# BAM_Reference_R2_1_1.net
KiCad netlist of a schematic drawn in EAGLE
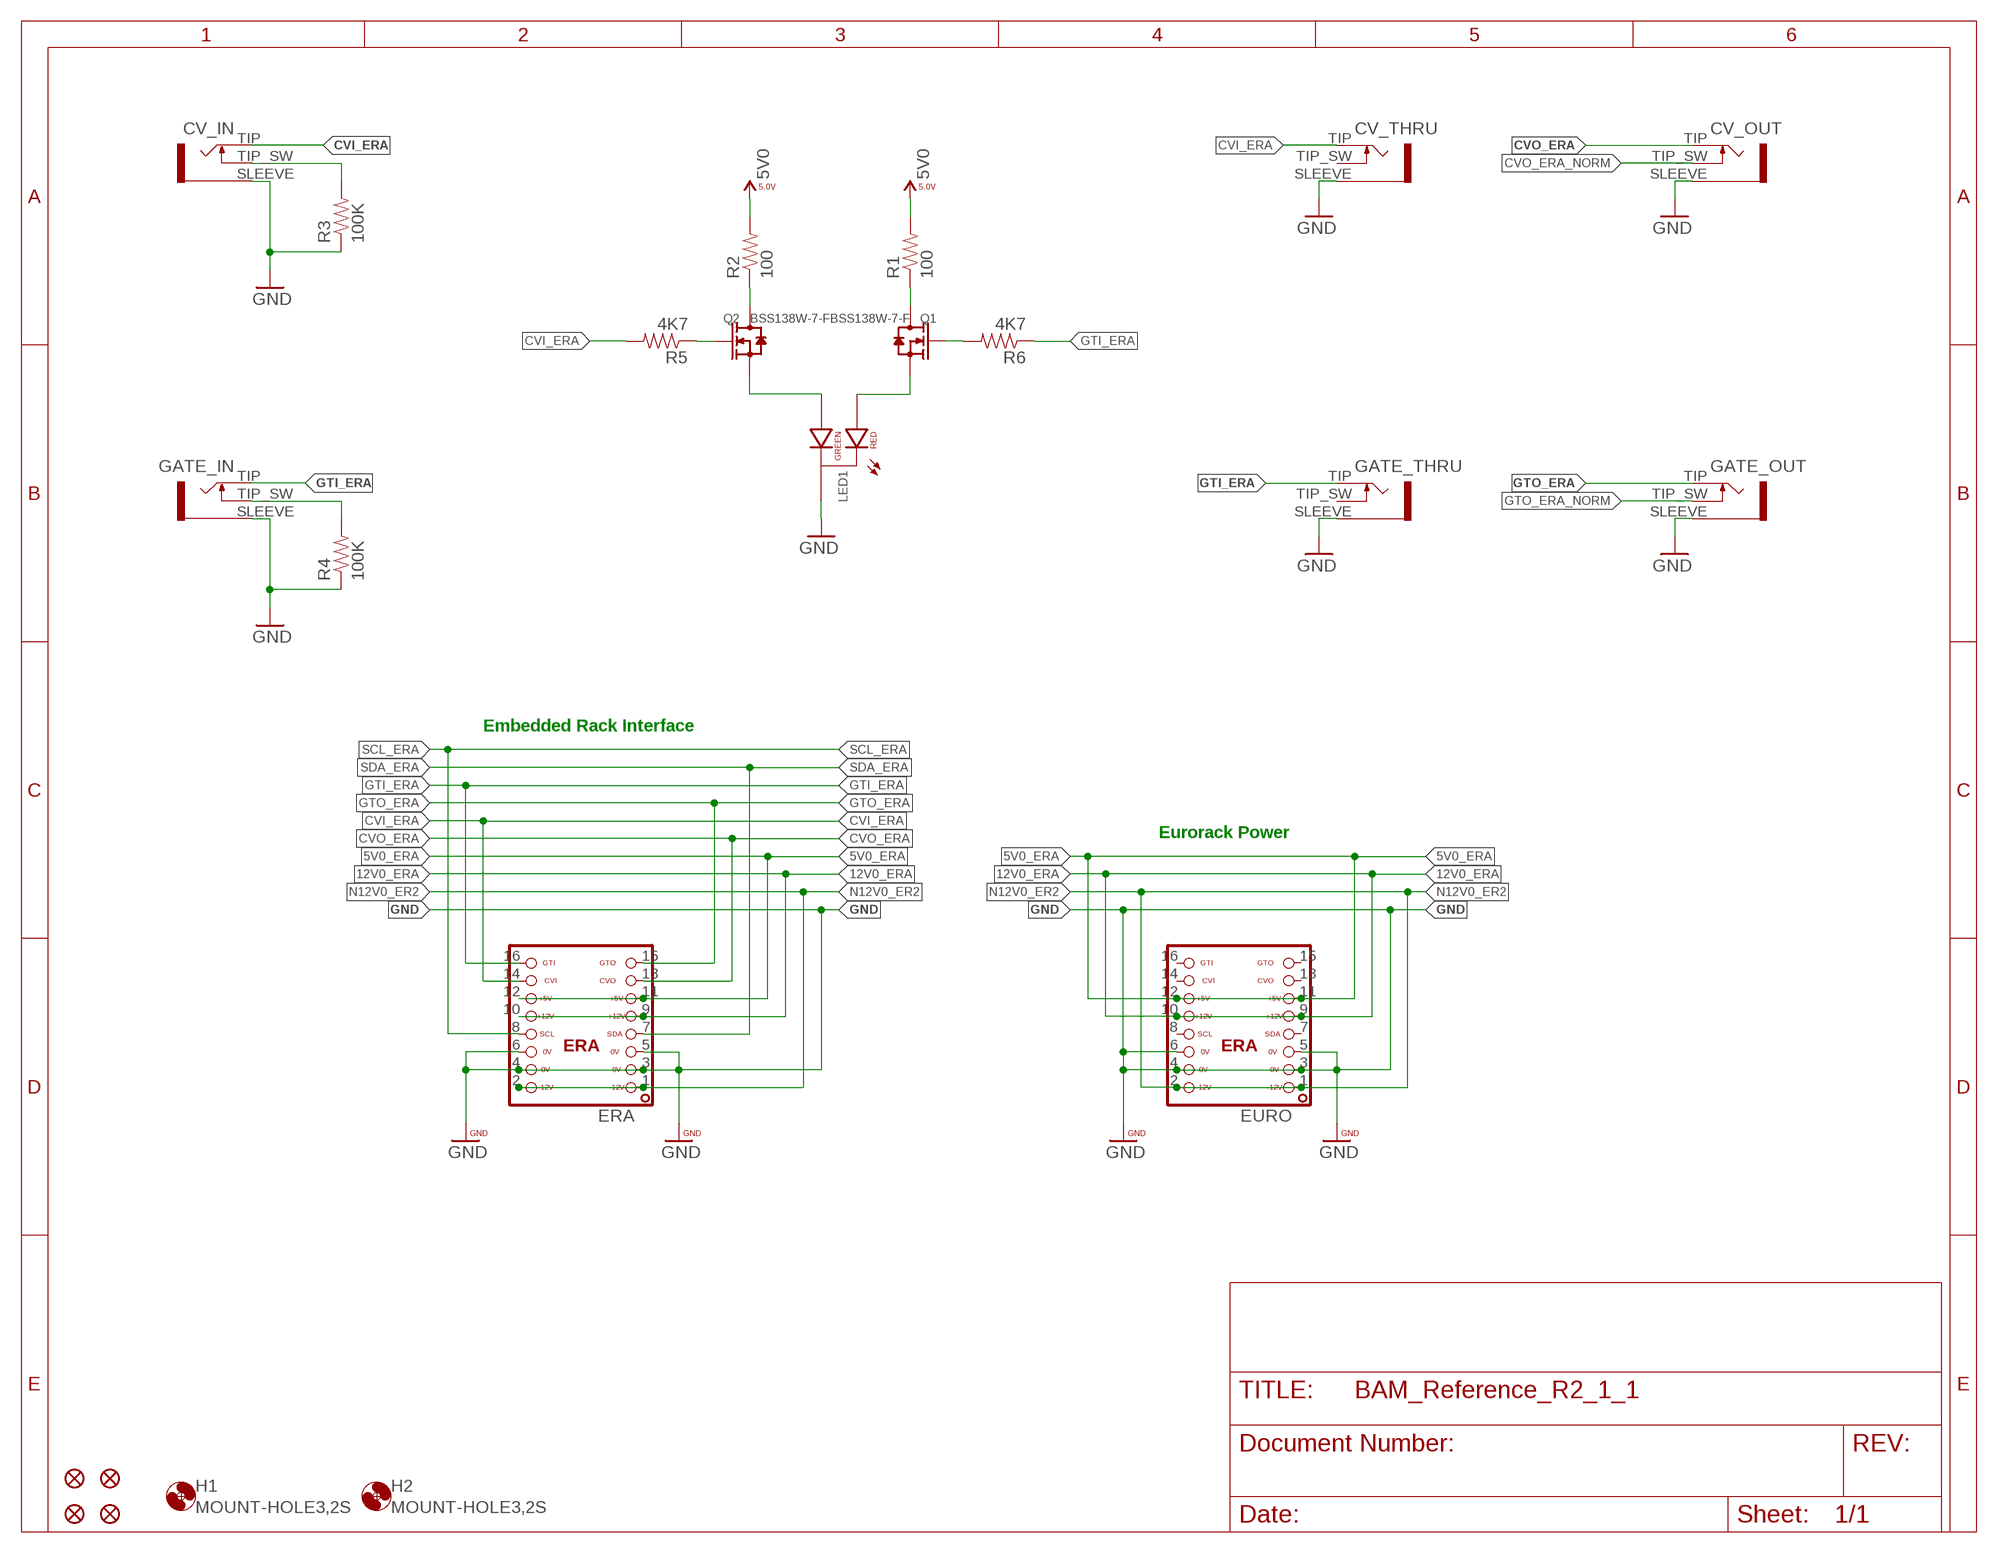
[diagram p0: schematic, sheet 1]

(export (version "E")
  (design (tool "Eeschema 10.0.6"))
  (components
    (comp (ref "CV_IN")
      (value "JACK-3_5MM-MONO-SW-MJ_3502")
      (footprint "eagle-import:MJ-3502")
      (libsource (lib "eagle-import") (part "oXo_Connectors_JACK-3_5MM-MONO-SW-MJ_3502"))
    )
    (comp (ref "CV_OUT")
      (value "JACK-3_5MM-MONO-SW-MJ_3502")
      (footprint "eagle-import:MJ-3502")
      (libsource (lib "eagle-import") (part "JACK-3_5MM-MONO-SW-MJ_3502"))
    )
    (comp (ref "CV_THRU")
      (value "JACK-3_5MM-MONO-SW-MJ_3502")
      (footprint "eagle-import:MJ-3502")
      (libsource (lib "eagle-import") (part "JACK-3_5MM-MONO-SW-MJ_3502"))
    )
    (comp (ref "ERA")
      (value "ERA-SHROUD")
      (footprint "eagle-import:ERA")
      (libsource (lib "eagle-import") (part "ERA-SHROUD"))
    )
    (comp (ref "EURO")
      (value "ERA-SHROUD")
      (footprint "eagle-import:ERA")
      (libsource (lib "eagle-import") (part "ERA-SHROUD"))
    )
    (comp (ref "FID1")
      (value "FIDUCIALUFIDUCIAL")
      (footprint "eagle-import:MICRO-FIDUCIAL")
      (libsource (lib "eagle-import") (part "FIDUCIALUFIDUCIAL"))
    )
    (comp (ref "FID2")
      (value "FIDUCIALUFIDUCIAL")
      (footprint "eagle-import:MICRO-FIDUCIAL")
      (libsource (lib "eagle-import") (part "FIDUCIALUFIDUCIAL"))
    )
    (comp (ref "FID3")
      (value "FIDUCIALUFIDUCIAL")
      (footprint "eagle-import:MICRO-FIDUCIAL")
      (libsource (lib "eagle-import") (part "FIDUCIALUFIDUCIAL"))
    )
    (comp (ref "FID4")
      (value "FIDUCIALUFIDUCIAL")
      (footprint "eagle-import:MICRO-FIDUCIAL")
      (libsource (lib "eagle-import") (part "FIDUCIALUFIDUCIAL"))
    )
    (comp (ref "GATE_IN")
      (value "JACK-3_5MM-MONO-SW-MJ_3502")
      (footprint "eagle-import:MJ-3502")
      (libsource (lib "eagle-import") (part "oXo_Connectors_JACK-3_5MM-MONO-SW-MJ_3502"))
    )
    (comp (ref "GATE_OUT")
      (value "JACK-3_5MM-MONO-SW-MJ_3502")
      (footprint "eagle-import:MJ-3502")
      (libsource (lib "eagle-import") (part "JACK-3_5MM-MONO-SW-MJ_3502"))
    )
    (comp (ref "GATE_THRU")
      (value "JACK-3_5MM-MONO-SW-MJ_3502")
      (footprint "eagle-import:MJ-3502")
      (libsource (lib "eagle-import") (part "JACK-3_5MM-MONO-SW-MJ_3502"))
    )
    (comp (ref "H1")
      (value "MOUNT-HOLE3,2S")
      (footprint "eagle-import:3,2,SMALL")
      (libsource (lib "eagle-import") (part "MOUNT-HOLE3,2S"))
    )
    (comp (ref "H2")
      (value "MOUNT-HOLE3,2S")
      (footprint "eagle-import:3,2,SMALL")
      (libsource (lib "eagle-import") (part "MOUNT-HOLE3,2S"))
    )
    (comp (ref "LED1")
      (value "LED-RG-CC-PTH-G18500")
      (footprint "eagle-import:LED-RG-PANEL")
      (libsource (lib "eagle-import") (part "LED-RG-CC-PTH-G18500"))
    )
    (comp (ref "Q1")
      (value "BSS138W-7-F")
      (footprint "eagle-import:SOT-23")
      (libsource (lib "eagle-import") (part "SMD-MOSFET-N-CH-50V-200MA-BSS138W-7-F(SOT-23)"))
    )
    (comp (ref "Q2")
      (value "BSS138W-7-F")
      (footprint "eagle-import:SOT-23")
      (libsource (lib "eagle-import") (part "SMD-MOSFET-N-CH-50V-200MA-BSS138W-7-F(SOT-23)"))
    )
    (comp (ref "R1")
      (value "100")
      (footprint "eagle-import:0603-RES")
      (libsource (lib "eagle-import") (part "RESISTOR0603"))
    )
    (comp (ref "R2")
      (value "100")
      (footprint "eagle-import:0603-RES")
      (libsource (lib "eagle-import") (part "RESISTOR0603"))
    )
    (comp (ref "R3")
      (value "100K")
      (footprint "eagle-import:0603-RES")
      (libsource (lib "eagle-import") (part "RESISTOR0603"))
    )
    (comp (ref "R4")
      (value "100K")
      (footprint "eagle-import:0603-RES")
      (libsource (lib "eagle-import") (part "RESISTOR0603"))
    )
    (comp (ref "R5")
      (value "4K7")
      (footprint "eagle-import:0603-RES")
      (libsource (lib "eagle-import") (part "RESISTOR0603"))
    )
    (comp (ref "R6")
      (value "4K7")
      (footprint "eagle-import:0603-RES")
      (libsource (lib "eagle-import") (part "RESISTOR0603"))
    )
  )
  (nets
    (net (code "1") (name "5V0") (class "Default")
      (node (ref "R1") (pin "2") (pinfunction "2_2") (pintype "passive"))
      (node (ref "R2") (pin "2") (pinfunction "2_2") (pintype "passive"))
    )
    (net (code "2") (name "5V0_ERA") (class "Default")
      (node (ref "ERA") (pin "11") (pinfunction "11_11") (pintype "passive"))
      (node (ref "ERA") (pin "12") (pinfunction "12_12") (pintype "passive"))
      (node (ref "EURO") (pin "11") (pinfunction "11_11") (pintype "passive"))
      (node (ref "EURO") (pin "12") (pinfunction "12_12") (pintype "passive"))
    )
    (net (code "3") (name "12V0_ERA") (class "Default")
      (node (ref "ERA") (pin "10") (pinfunction "10_10") (pintype "passive"))
      (node (ref "ERA") (pin "9") (pinfunction "9_9") (pintype "passive"))
      (node (ref "EURO") (pin "10") (pinfunction "10_10") (pintype "passive"))
      (node (ref "EURO") (pin "9") (pinfunction "9_9") (pintype "passive"))
    )
    (net (code "4") (name "CVI_ERA") (class "Default")
      (node (ref "CV_IN") (pin "TIP") (pinfunction "TIP_TIP") (pintype "passive"))
      (node (ref "CV_THRU") (pin "TIP") (pinfunction "TIP_TIP") (pintype "passive"))
      (node (ref "ERA") (pin "14") (pinfunction "14_14") (pintype "passive"))
      (node (ref "R5") (pin "2") (pinfunction "2_2") (pintype "passive"))
    )
    (net (code "5") (name "CVO_ERA") (class "Default")
      (node (ref "CV_OUT") (pin "TIP") (pinfunction "TIP_TIP") (pintype "passive"))
      (node (ref "ERA") (pin "13") (pinfunction "13_13") (pintype "passive"))
    )
    (net (code "6") (name "CVO_ERA_NORM") (class "Default")
      (node (ref "CV_OUT") (pin "TIP_SW") (pinfunction "TIP_SW_TIP_SW") (pintype "passive"))
    )
    (net (code "7") (name "GND") (class "Default")
      (node (ref "CV_IN") (pin "SLEEVE") (pinfunction "SLEEVE_SLEEVE") (pintype "passive"))
      (node (ref "CV_OUT") (pin "SLEEVE") (pinfunction "SLEEVE_SLEEVE") (pintype "passive"))
      (node (ref "CV_THRU") (pin "SLEEVE") (pinfunction "SLEEVE_SLEEVE") (pintype "passive"))
      (node (ref "ERA") (pin "3") (pinfunction "3_3") (pintype "passive"))
      (node (ref "ERA") (pin "4") (pinfunction "4_4") (pintype "passive"))
      (node (ref "ERA") (pin "5") (pinfunction "5_5") (pintype "passive"))
      (node (ref "ERA") (pin "6") (pinfunction "6_6") (pintype "passive"))
      (node (ref "EURO") (pin "3") (pinfunction "3_3") (pintype "passive"))
      (node (ref "EURO") (pin "4") (pinfunction "4_4") (pintype "passive"))
      (node (ref "EURO") (pin "5") (pinfunction "5_5") (pintype "passive"))
      (node (ref "EURO") (pin "6") (pinfunction "6_6") (pintype "passive"))
      (node (ref "GATE_IN") (pin "SLEEVE") (pinfunction "SLEEVE_SLEEVE") (pintype "passive"))
      (node (ref "GATE_OUT") (pin "SLEEVE") (pinfunction "SLEEVE_SLEEVE") (pintype "passive"))
      (node (ref "GATE_THRU") (pin "SLEEVE") (pinfunction "SLEEVE_SLEEVE") (pintype "passive"))
      (node (ref "LED1") (pin "CC") (pinfunction "CATHODE_CC") (pintype "bidirectional"))
      (node (ref "R3") (pin "1") (pinfunction "1_1") (pintype "passive"))
      (node (ref "R4") (pin "1") (pinfunction "1_1") (pintype "passive"))
    )
    (net (code "8") (name "GTI_ERA") (class "Default")
      (node (ref "ERA") (pin "16") (pinfunction "16_16") (pintype "passive"))
      (node (ref "GATE_IN") (pin "TIP") (pinfunction "TIP_TIP") (pintype "passive"))
      (node (ref "GATE_THRU") (pin "TIP") (pinfunction "TIP_TIP") (pintype "passive"))
      (node (ref "R6") (pin "1") (pinfunction "1_1") (pintype "passive"))
    )
    (net (code "9") (name "GTO_ERA") (class "Default")
      (node (ref "ERA") (pin "15") (pinfunction "15_15") (pintype "passive"))
      (node (ref "GATE_OUT") (pin "TIP") (pinfunction "TIP_TIP") (pintype "passive"))
    )
    (net (code "10") (name "GTO_ERA_NORM") (class "Default")
      (node (ref "GATE_OUT") (pin "TIP_SW") (pinfunction "TIP_SW_TIP_SW") (pintype "passive"))
    )
    (net (code "11") (name "N12V0_ER2") (class "Default")
      (node (ref "ERA") (pin "1") (pinfunction "1_1") (pintype "passive"))
      (node (ref "ERA") (pin "2") (pinfunction "2_2") (pintype "passive"))
      (node (ref "EURO") (pin "1") (pinfunction "1_1") (pintype "passive"))
      (node (ref "EURO") (pin "2") (pinfunction "2_2") (pintype "passive"))
    )
    (net (code "12") (name "Net-(CV_IN-PadTIP_SW)") (class "Default")
      (node (ref "CV_IN") (pin "TIP_SW") (pinfunction "TIP_SW_TIP_SW") (pintype "passive"))
      (node (ref "R3") (pin "2") (pinfunction "2_2") (pintype "passive"))
    )
    (net (code "13") (name "Net-(GATE_IN-PadTIP_SW)") (class "Default")
      (node (ref "GATE_IN") (pin "TIP_SW") (pinfunction "TIP_SW_TIP_SW") (pintype "passive"))
      (node (ref "R4") (pin "2") (pinfunction "2_2") (pintype "passive"))
    )
    (net (code "14") (name "Net-(LED1-GREEN_CATHODE)") (class "Default")
      (node (ref "LED1") (pin "GREEN") (pinfunction "GREEN_CATHODE_GREEN") (pintype "bidirectional"))
      (node (ref "Q2") (pin "2") (pinfunction "S_2") (pintype "passive"))
    )
    (net (code "15") (name "Net-(LED1-RED_CATHODE)") (class "Default")
      (node (ref "LED1") (pin "RED") (pinfunction "RED_CATHODE_RED") (pintype "bidirectional"))
      (node (ref "Q1") (pin "2") (pinfunction "S_2") (pintype "passive"))
    )
    (net (code "16") (name "Net-(Q1-D)") (class "Default")
      (node (ref "Q1") (pin "3") (pinfunction "D_3") (pintype "passive"))
      (node (ref "R1") (pin "1") (pinfunction "1_1") (pintype "passive"))
    )
    (net (code "17") (name "Net-(Q1-G)") (class "Default")
      (node (ref "Q1") (pin "1") (pinfunction "G_1") (pintype "passive"))
      (node (ref "R6") (pin "2") (pinfunction "2_2") (pintype "passive"))
    )
    (net (code "18") (name "Net-(Q2-D)") (class "Default")
      (node (ref "Q2") (pin "3") (pinfunction "D_3") (pintype "passive"))
      (node (ref "R2") (pin "1") (pinfunction "1_1") (pintype "passive"))
    )
    (net (code "19") (name "Net-(Q2-G)") (class "Default")
      (node (ref "Q2") (pin "1") (pinfunction "G_1") (pintype "passive"))
      (node (ref "R5") (pin "1") (pinfunction "1_1") (pintype "passive"))
    )
    (net (code "20") (name "SCL_ERA") (class "Default")
      (node (ref "ERA") (pin "8") (pinfunction "8_8") (pintype "passive"))
    )
    (net (code "21") (name "SDA_ERA") (class "Default")
      (node (ref "ERA") (pin "7") (pinfunction "7_7") (pintype "passive"))
    )
    (net (code "22") (name "unconnected-(CV_THRU-PadTIP_SW)") (class "Default")
      (node (ref "CV_THRU") (pin "TIP_SW") (pinfunction "TIP_SW_TIP_SW") (pintype "passive"))
    )
    (net (code "23") (name "unconnected-(EURO-Pad7)") (class "Default")
      (node (ref "EURO") (pin "7") (pinfunction "7_7") (pintype "passive"))
    )
    (net (code "24") (name "unconnected-(EURO-Pad8)") (class "Default")
      (node (ref "EURO") (pin "8") (pinfunction "8_8") (pintype "passive"))
    )
    (net (code "25") (name "unconnected-(EURO-Pad13)") (class "Default")
      (node (ref "EURO") (pin "13") (pinfunction "13_13") (pintype "passive"))
    )
    (net (code "26") (name "unconnected-(EURO-Pad14)") (class "Default")
      (node (ref "EURO") (pin "14") (pinfunction "14_14") (pintype "passive"))
    )
    (net (code "27") (name "unconnected-(EURO-Pad15)") (class "Default")
      (node (ref "EURO") (pin "15") (pinfunction "15_15") (pintype "passive"))
    )
    (net (code "28") (name "unconnected-(EURO-Pad16)") (class "Default")
      (node (ref "EURO") (pin "16") (pinfunction "16_16") (pintype "passive"))
    )
    (net (code "29") (name "unconnected-(GATE_THRU-PadTIP_SW)") (class "Default")
      (node (ref "GATE_THRU") (pin "TIP_SW") (pinfunction "TIP_SW_TIP_SW") (pintype "passive"))
    )
  )
)
